# PCM5102A_Breakout.net
KiCad netlist of a schematic drawn in EAGLE
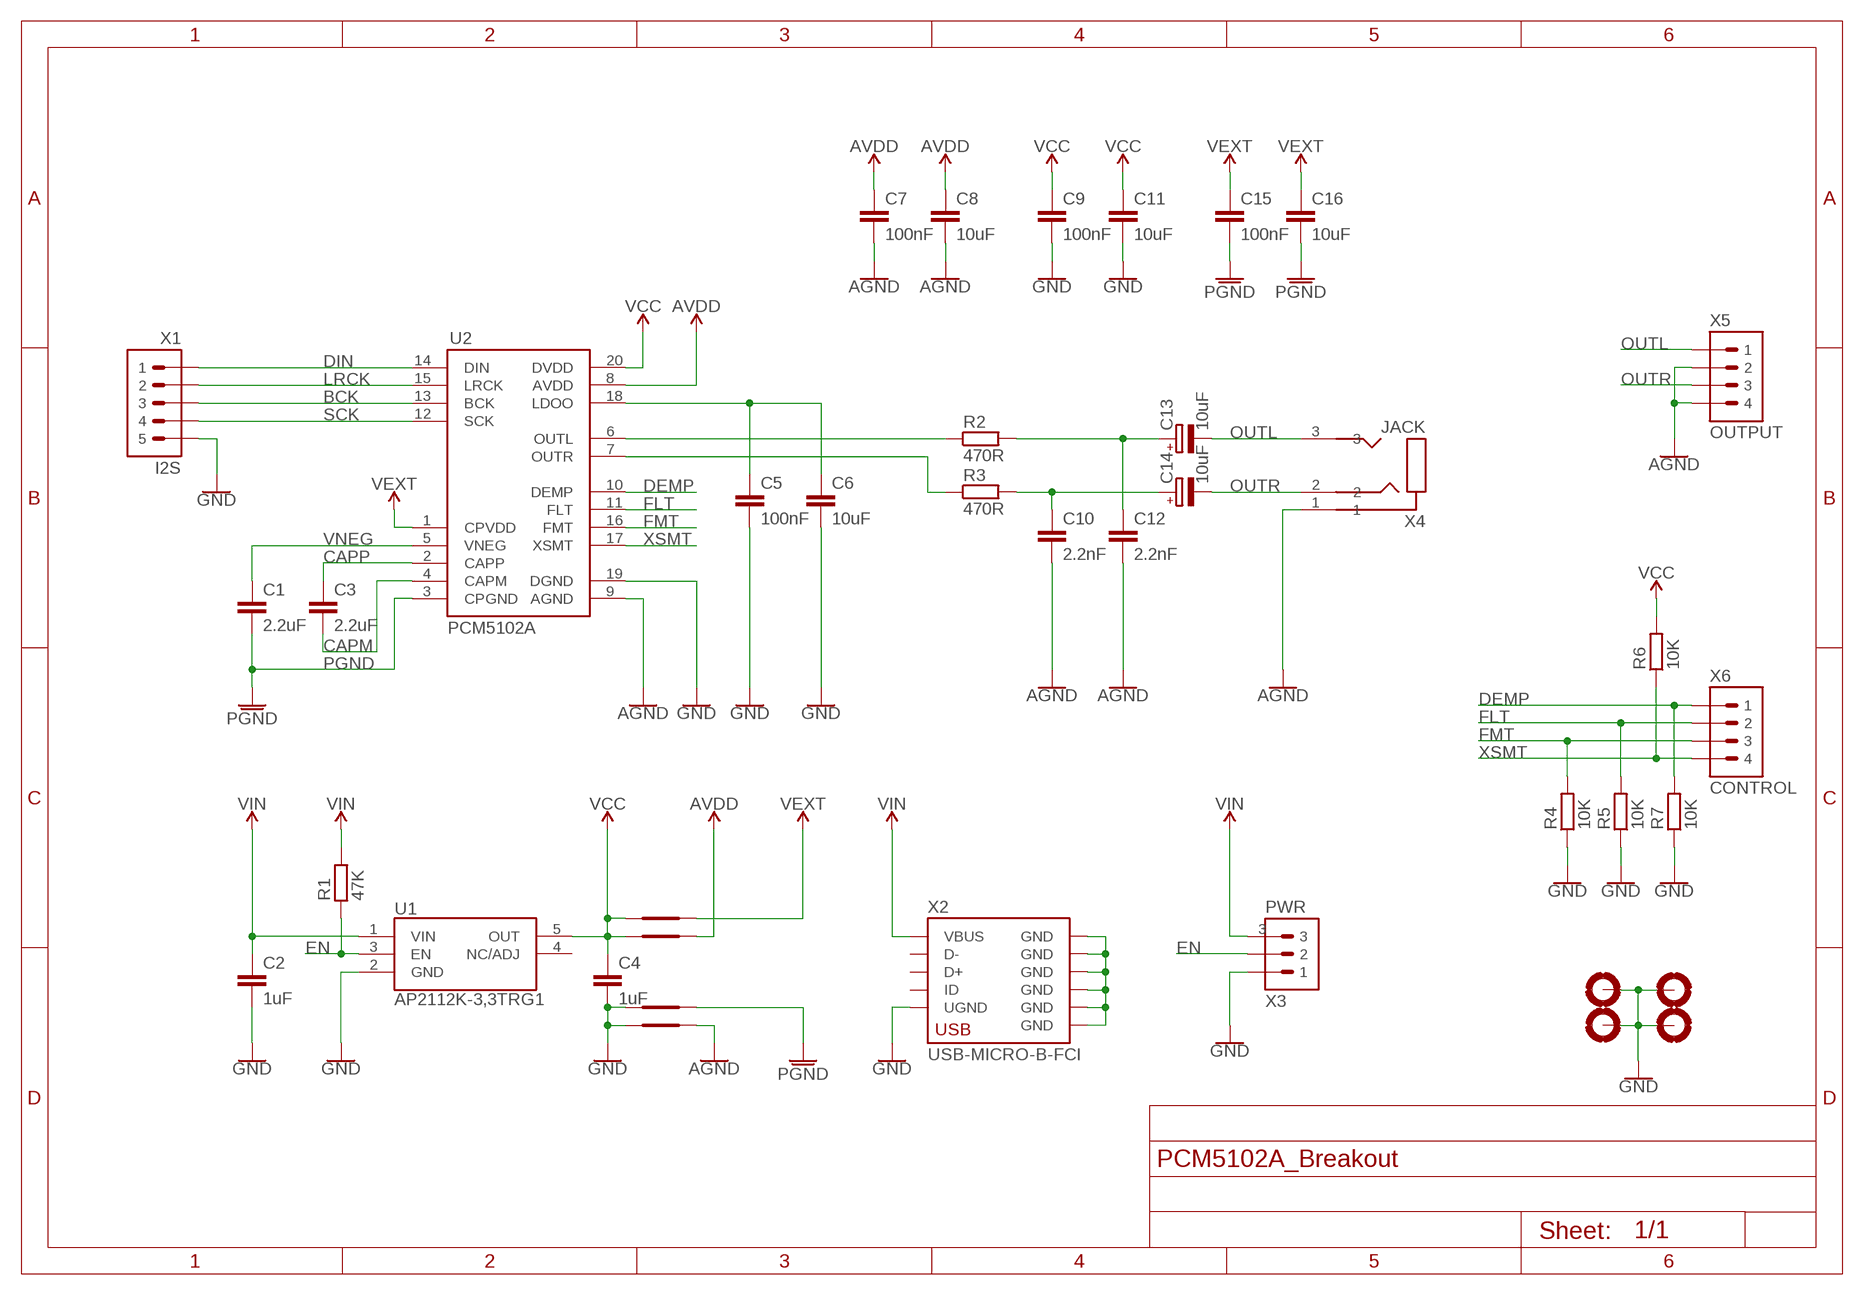
[diagram p0: schematic, sheet 1]

(export (version "E")
  (design (tool "Eeschema 10.0.6"))
  (components
    (comp (ref "C1")
      (value "2.2uF")
      (footprint "eagle-import:C0603")
      (libsource (lib "eagle-import") (part "CAPC0603"))
    )
    (comp (ref "C2")
      (value "1uF")
      (footprint "eagle-import:C0603")
      (libsource (lib "eagle-import") (part "CAPC0603"))
    )
    (comp (ref "C3")
      (value "2.2uF")
      (footprint "eagle-import:C0603")
      (libsource (lib "eagle-import") (part "CAPC0603"))
    )
    (comp (ref "C4")
      (value "1uF")
      (footprint "eagle-import:C0603")
      (libsource (lib "eagle-import") (part "CAPC0603"))
    )
    (comp (ref "C5")
      (value "100nF")
      (footprint "eagle-import:C0603")
      (libsource (lib "eagle-import") (part "CAPC0603"))
    )
    (comp (ref "C6")
      (value "10uF")
      (footprint "eagle-import:C0603")
      (libsource (lib "eagle-import") (part "CAPC0603"))
    )
    (comp (ref "C7")
      (value "100nF")
      (footprint "eagle-import:C0603")
      (libsource (lib "eagle-import") (part "CAPC0603"))
    )
    (comp (ref "C8")
      (value "10uF")
      (footprint "eagle-import:C0603")
      (libsource (lib "eagle-import") (part "CAPC0603"))
    )
    (comp (ref "C9")
      (value "100nF")
      (footprint "eagle-import:C0603")
      (libsource (lib "eagle-import") (part "CAPC0603"))
    )
    (comp (ref "C10")
      (value "2.2nF")
      (footprint "eagle-import:C0603")
      (libsource (lib "eagle-import") (part "CAPC0603"))
    )
    (comp (ref "C11")
      (value "10uF")
      (footprint "eagle-import:C0603")
      (libsource (lib "eagle-import") (part "CAPC0603"))
    )
    (comp (ref "C12")
      (value "2.2nF")
      (footprint "eagle-import:C0603")
      (libsource (lib "eagle-import") (part "CAPC0603"))
    )
    (comp (ref "C13")
      (value "10uF")
      (footprint "eagle-import:ROQANG-RVT0405")
      (libsource (lib "eagle-import") (part "CAP-POL-ALUMROQANG-RVT0405"))
    )
    (comp (ref "C14")
      (value "10uF")
      (footprint "eagle-import:ROQANG-RVT0405")
      (libsource (lib "eagle-import") (part "CAP-POL-ALUMROQANG-RVT0405"))
    )
    (comp (ref "C15")
      (value "100nF")
      (footprint "eagle-import:C0603")
      (libsource (lib "eagle-import") (part "CAPC0603"))
    )
    (comp (ref "C16")
      (value "10uF")
      (footprint "eagle-import:C0603")
      (libsource (lib "eagle-import") (part "CAPC0603"))
    )
    (comp (ref "H1")
      (value "MOUNTHOLE-PAD3.2")
      (footprint "eagle-import:3.2-PAD")
      (libsource (lib "eagle-import") (part "MOUNTHOLE-PAD3.2"))
    )
    (comp (ref "H2")
      (value "MOUNTHOLE-PAD3.2")
      (footprint "eagle-import:3.2-PAD")
      (libsource (lib "eagle-import") (part "MOUNTHOLE-PAD3.2"))
    )
    (comp (ref "H3")
      (value "MOUNTHOLE-PAD3.2")
      (footprint "eagle-import:3.2-PAD")
      (libsource (lib "eagle-import") (part "MOUNTHOLE-PAD3.2"))
    )
    (comp (ref "H4")
      (value "MOUNTHOLE-PAD3.2")
      (footprint "eagle-import:3.2-PAD")
      (libsource (lib "eagle-import") (part "MOUNTHOLE-PAD3.2"))
    )
    (comp (ref "R1")
      (value "47K")
      (footprint "eagle-import:R0603")
      (libsource (lib "eagle-import") (part "RESISTOR0603"))
    )
    (comp (ref "R2")
      (value "470R")
      (footprint "eagle-import:R0603")
      (libsource (lib "eagle-import") (part "RESISTOR0603"))
    )
    (comp (ref "R3")
      (value "470R")
      (footprint "eagle-import:R0603")
      (libsource (lib "eagle-import") (part "RESISTOR0603"))
    )
    (comp (ref "R4")
      (value "10K")
      (footprint "eagle-import:R0603")
      (libsource (lib "eagle-import") (part "RESISTOR0603"))
    )
    (comp (ref "R5")
      (value "10K")
      (footprint "eagle-import:R0603")
      (libsource (lib "eagle-import") (part "RESISTOR0603"))
    )
    (comp (ref "R6")
      (value "10K")
      (footprint "eagle-import:R0603")
      (libsource (lib "eagle-import") (part "RESISTOR0603"))
    )
    (comp (ref "R7")
      (value "10K")
      (footprint "eagle-import:R0603")
      (libsource (lib "eagle-import") (part "RESISTOR0603"))
    )
    (comp (ref "SH1")
      (value "SHORT-SMD-06096")
      (footprint "eagle-import:SHORT-SMD-06096")
      (libsource (lib "eagle-import") (part "SHORT-SMD-06096"))
    )
    (comp (ref "SH2")
      (value "SHORT-SMD-06096")
      (footprint "eagle-import:SHORT-SMD-06096")
      (libsource (lib "eagle-import") (part "SHORT-SMD-06096"))
    )
    (comp (ref "SH3")
      (value "SHORT-SMD-06096")
      (footprint "eagle-import:SHORT-SMD-06096")
      (libsource (lib "eagle-import") (part "SHORT-SMD-06096"))
    )
    (comp (ref "SH4")
      (value "SHORT-SMD-06096")
      (footprint "eagle-import:SHORT-SMD-06096")
      (libsource (lib "eagle-import") (part "SHORT-SMD-06096"))
    )
    (comp (ref "U1")
      (value "AP2112K-3,3TRG1")
      (footprint "eagle-import:SOT23-5")
      (libsource (lib "eagle-import") (part "REGULATOR-AP2112KK-SOT23-5"))
    )
    (comp (ref "U2")
      (value "PCM5102A")
      (footprint "eagle-import:TSSOP-20")
      (libsource (lib "eagle-import") (part "PCM5102APWR"))
    )
    (comp (ref "X1")
      (value "I2S")
      (footprint "eagle-import:1X05-2.54")
      (libsource (lib "eagle-import") (part "HEADER-1X05-2.54"))
    )
    (comp (ref "X2")
      (value "USB-MICRO-B-FCI")
      (footprint "eagle-import:USB-MICRO-B-FCI")
      (libsource (lib "eagle-import") (part "USB-MICRO-B-FCI"))
    )
    (comp (ref "X3")
      (value "PWR")
      (footprint "eagle-import:1X03P-2.54")
      (libsource (lib "eagle-import") (part "HEADER-1X03-2.54P"))
    )
    (comp (ref "X4")
      (value "JACK")
      (footprint "eagle-import:AUDIO-3.5-SJ1-3523N")
      (libsource (lib "eagle-import") (part "AUDIO-3.5-SJ1-3523N"))
    )
    (comp (ref "X5")
      (value "OUTPUT")
      (footprint "eagle-import:1X04-2.54")
      (libsource (lib "eagle-import") (part "HEADER-1X04-2.54"))
    )
    (comp (ref "X6")
      (value "CONTROL")
      (footprint "eagle-import:1X04-2.54")
      (libsource (lib "eagle-import") (part "HEADER-1X04-2.54"))
    )
  )
  (nets
    (net (code "1") (name "/BCK") (class "Default")
      (node (ref "U2") (pin "13") (pinfunction "BCK_13") (pintype "bidirectional"))
      (node (ref "X1") (pin "3") (pinfunction "3_3") (pintype "passive"))
    )
    (net (code "2") (name "/CAPM") (class "Default")
      (node (ref "C3") (pin "2") (pinfunction "2_2") (pintype "passive"))
      (node (ref "U2") (pin "4") (pinfunction "CAPM_4") (pintype "bidirectional"))
    )
    (net (code "3") (name "/CAPP") (class "Default")
      (node (ref "C3") (pin "1") (pinfunction "1_1") (pintype "passive"))
      (node (ref "U2") (pin "2") (pinfunction "CAPP_2") (pintype "bidirectional"))
    )
    (net (code "4") (name "/DEMP") (class "Default")
      (node (ref "R7") (pin "2") (pinfunction "2_2") (pintype "passive"))
      (node (ref "U2") (pin "10") (pinfunction "DEMP_10") (pintype "bidirectional"))
      (node (ref "X6") (pin "1") (pinfunction "1_1") (pintype "passive"))
    )
    (net (code "5") (name "/DIN") (class "Default")
      (node (ref "U2") (pin "14") (pinfunction "DIN_14") (pintype "input"))
      (node (ref "X1") (pin "1") (pinfunction "1_1") (pintype "passive"))
    )
    (net (code "6") (name "/EN") (class "Default")
      (node (ref "R1") (pin "1") (pinfunction "1_1") (pintype "passive"))
      (node (ref "U1") (pin "3") (pinfunction "EN_3") (pintype "input"))
      (node (ref "X3") (pin "2") (pinfunction "2_2") (pintype "passive"))
    )
    (net (code "7") (name "/FLT") (class "Default")
      (node (ref "R5") (pin "2") (pinfunction "2_2") (pintype "passive"))
      (node (ref "U2") (pin "11") (pinfunction "FLT_11") (pintype "bidirectional"))
      (node (ref "X6") (pin "2") (pinfunction "2_2") (pintype "passive"))
    )
    (net (code "8") (name "/FMT") (class "Default")
      (node (ref "R4") (pin "2") (pinfunction "2_2") (pintype "passive"))
      (node (ref "U2") (pin "16") (pinfunction "FMT_16") (pintype "bidirectional"))
      (node (ref "X6") (pin "3") (pinfunction "3_3") (pintype "passive"))
    )
    (net (code "9") (name "/LRCK") (class "Default")
      (node (ref "U2") (pin "15") (pinfunction "LRCK_15") (pintype "bidirectional"))
      (node (ref "X1") (pin "2") (pinfunction "2_2") (pintype "passive"))
    )
    (net (code "10") (name "/OUTL") (class "Default")
      (node (ref "C13") (pin "-") (pinfunction "-_-") (pintype "passive"))
      (node (ref "X4") (pin "3") (pinfunction "3_3") (pintype "bidirectional"))
      (node (ref "X5") (pin "1") (pinfunction "1_1") (pintype "passive"))
    )
    (net (code "11") (name "/OUTR") (class "Default")
      (node (ref "C14") (pin "-") (pinfunction "-_-") (pintype "passive"))
      (node (ref "X4") (pin "2") (pinfunction "2_2") (pintype "bidirectional"))
      (node (ref "X5") (pin "3") (pinfunction "3_3") (pintype "passive"))
    )
    (net (code "12") (name "/SCK") (class "Default")
      (node (ref "U2") (pin "12") (pinfunction "SCK_12") (pintype "input"))
      (node (ref "X1") (pin "4") (pinfunction "4_4") (pintype "passive"))
    )
    (net (code "13") (name "/VNEG") (class "Default")
      (node (ref "C1") (pin "1") (pinfunction "1_1") (pintype "passive"))
      (node (ref "U2") (pin "5") (pinfunction "VNEG_5") (pintype "bidirectional"))
    )
    (net (code "14") (name "/XSMT") (class "Default")
      (node (ref "R6") (pin "1") (pinfunction "1_1") (pintype "passive"))
      (node (ref "U2") (pin "17") (pinfunction "XSMT_17") (pintype "bidirectional"))
      (node (ref "X6") (pin "4") (pinfunction "4_4") (pintype "passive"))
    )
    (net (code "15") (name "AGND") (class "Default")
      (node (ref "C10") (pin "2") (pinfunction "2_2") (pintype "passive"))
      (node (ref "C12") (pin "2") (pinfunction "2_2") (pintype "passive"))
      (node (ref "C7") (pin "2") (pinfunction "2_2") (pintype "passive"))
      (node (ref "C8") (pin "2") (pinfunction "2_2") (pintype "passive"))
      (node (ref "SH4") (pin "2") (pinfunction "P$2_2") (pintype "bidirectional"))
      (node (ref "U2") (pin "9") (pinfunction "AGND_9") (pintype "bidirectional"))
      (node (ref "X4") (pin "1") (pinfunction "1_1") (pintype "bidirectional"))
      (node (ref "X5") (pin "2") (pinfunction "2_2") (pintype "passive"))
      (node (ref "X5") (pin "4") (pinfunction "4_4") (pintype "passive"))
    )
    (net (code "16") (name "AVDD") (class "Default")
      (node (ref "C7") (pin "1") (pinfunction "1_1") (pintype "passive"))
      (node (ref "C8") (pin "1") (pinfunction "1_1") (pintype "passive"))
      (node (ref "SH2") (pin "2") (pinfunction "P$2_2") (pintype "bidirectional"))
      (node (ref "U2") (pin "8") (pinfunction "AVDD_8") (pintype "bidirectional"))
    )
    (net (code "17") (name "GND") (class "Default")
      (node (ref "C11") (pin "2") (pinfunction "2_2") (pintype "passive"))
      (node (ref "C2") (pin "2") (pinfunction "2_2") (pintype "passive"))
      (node (ref "C4") (pin "2") (pinfunction "2_2") (pintype "passive"))
      (node (ref "C5") (pin "2") (pinfunction "2_2") (pintype "passive"))
      (node (ref "C6") (pin "2") (pinfunction "2_2") (pintype "passive"))
      (node (ref "C9") (pin "2") (pinfunction "2_2") (pintype "passive"))
      (node (ref "H1") (pin "B3,2") (pinfunction "MOUNT_B3,2") (pintype "passive"))
      (node (ref "H2") (pin "B3,2") (pinfunction "MOUNT_B3,2") (pintype "passive"))
      (node (ref "H3") (pin "B3,2") (pinfunction "MOUNT_B3,2") (pintype "passive"))
      (node (ref "H4") (pin "B3,2") (pinfunction "MOUNT_B3,2") (pintype "passive"))
      (node (ref "R4") (pin "1") (pinfunction "1_1") (pintype "passive"))
      (node (ref "R5") (pin "1") (pinfunction "1_1") (pintype "passive"))
      (node (ref "R7") (pin "1") (pinfunction "1_1") (pintype "passive"))
      (node (ref "SH3") (pin "1") (pinfunction "P$1_1") (pintype "bidirectional"))
      (node (ref "SH4") (pin "1") (pinfunction "P$1_1") (pintype "bidirectional"))
      (node (ref "U1") (pin "2") (pinfunction "GND_2") (pintype "power_in"))
      (node (ref "U2") (pin "19") (pinfunction "DGND_19") (pintype "bidirectional"))
      (node (ref "X1") (pin "5") (pinfunction "5_5") (pintype "passive"))
      (node (ref "X2") (pin "5") (pinfunction "UGND_5") (pintype "power_in"))
      (node (ref "X3") (pin "1") (pinfunction "1_1") (pintype "passive"))
    )
    (net (code "18") (name "Net-(C10-Pad1)") (class "Default")
      (node (ref "C10") (pin "1") (pinfunction "1_1") (pintype "passive"))
      (node (ref "C14") (pin "+") (pinfunction "+_+") (pintype "passive"))
      (node (ref "R3") (pin "2") (pinfunction "2_2") (pintype "passive"))
    )
    (net (code "19") (name "Net-(C12-Pad1)") (class "Default")
      (node (ref "C12") (pin "1") (pinfunction "1_1") (pintype "passive"))
      (node (ref "C13") (pin "+") (pinfunction "+_+") (pintype "passive"))
      (node (ref "R2") (pin "2") (pinfunction "2_2") (pintype "passive"))
    )
    (net (code "20") (name "Net-(U2-LDOO)") (class "Default")
      (node (ref "C5") (pin "1") (pinfunction "1_1") (pintype "passive"))
      (node (ref "C6") (pin "1") (pinfunction "1_1") (pintype "passive"))
      (node (ref "U2") (pin "18") (pinfunction "LDOO_18") (pintype "bidirectional"))
    )
    (net (code "21") (name "Net-(U2-OUTL)") (class "Default")
      (node (ref "R2") (pin "1") (pinfunction "1_1") (pintype "passive"))
      (node (ref "U2") (pin "6") (pinfunction "OUTL_6") (pintype "bidirectional"))
    )
    (net (code "22") (name "Net-(U2-OUTR)") (class "Default")
      (node (ref "R3") (pin "1") (pinfunction "1_1") (pintype "passive"))
      (node (ref "U2") (pin "7") (pinfunction "OUTR_7") (pintype "bidirectional"))
    )
    (net (code "23") (name "Net-(X2-GND-PadGND@1)") (class "Default")
      (node (ref "X2") (pin "GND@1") (pinfunction "GND_GND@1") (pintype "power_in"))
      (node (ref "X2") (pin "GND@2") (pinfunction "GND_GND@2") (pintype "power_in"))
      (node (ref "X2") (pin "GND@3") (pinfunction "GND_GND@3") (pintype "power_in"))
      (node (ref "X2") (pin "GND@4") (pinfunction "GND_GND@4") (pintype "power_in"))
      (node (ref "X2") (pin "GND@5") (pinfunction "GND_GND@5") (pintype "power_in"))
      (node (ref "X2") (pin "GND@6") (pinfunction "GND_GND@6") (pintype "power_in"))
    )
    (net (code "24") (name "PGND") (class "Default")
      (node (ref "C1") (pin "2") (pinfunction "2_2") (pintype "passive"))
      (node (ref "C15") (pin "2") (pinfunction "2_2") (pintype "passive"))
      (node (ref "C16") (pin "2") (pinfunction "2_2") (pintype "passive"))
      (node (ref "SH3") (pin "2") (pinfunction "P$2_2") (pintype "bidirectional"))
      (node (ref "U2") (pin "3") (pinfunction "CPGND_3") (pintype "bidirectional"))
    )
    (net (code "25") (name "VCC") (class "Default")
      (node (ref "C11") (pin "1") (pinfunction "1_1") (pintype "passive"))
      (node (ref "C4") (pin "1") (pinfunction "1_1") (pintype "passive"))
      (node (ref "C9") (pin "1") (pinfunction "1_1") (pintype "passive"))
      (node (ref "R6") (pin "2") (pinfunction "2_2") (pintype "passive"))
      (node (ref "SH1") (pin "1") (pinfunction "P$1_1") (pintype "bidirectional"))
      (node (ref "SH2") (pin "1") (pinfunction "P$1_1") (pintype "bidirectional"))
      (node (ref "U1") (pin "5") (pinfunction "OUT_5") (pintype "power_in"))
      (node (ref "U2") (pin "20") (pinfunction "DVDD_20") (pintype "bidirectional"))
    )
    (net (code "26") (name "VEXT") (class "Default")
      (node (ref "C15") (pin "1") (pinfunction "1_1") (pintype "passive"))
      (node (ref "C16") (pin "1") (pinfunction "1_1") (pintype "passive"))
      (node (ref "SH1") (pin "2") (pinfunction "P$2_2") (pintype "bidirectional"))
      (node (ref "U2") (pin "1") (pinfunction "CPVDD_1") (pintype "bidirectional"))
    )
    (net (code "27") (name "VIN") (class "Default")
      (node (ref "C2") (pin "1") (pinfunction "1_1") (pintype "passive"))
      (node (ref "R1") (pin "2") (pinfunction "2_2") (pintype "passive"))
      (node (ref "U1") (pin "1") (pinfunction "VIN_1") (pintype "power_in"))
      (node (ref "X2") (pin "1") (pinfunction "VBUS_1") (pintype "power_in"))
      (node (ref "X3") (pin "3") (pinfunction "3_3") (pintype "passive"))
    )
    (net (code "28") (name "unconnected-(U1-NC{slash}ADJ-Pad4)") (class "Default")
      (node (ref "U1") (pin "4") (pinfunction "NC/ADJ_4") (pintype "passive"))
    )
    (net (code "29") (name "unconnected-(X2-D+-Pad3)") (class "Default")
      (node (ref "X2") (pin "3") (pinfunction "D+_3") (pintype "bidirectional"))
    )
    (net (code "30") (name "unconnected-(X2-D--Pad2)") (class "Default")
      (node (ref "X2") (pin "2") (pinfunction "D-_2") (pintype "bidirectional"))
    )
    (net (code "31") (name "unconnected-(X2-ID-Pad4)") (class "Default")
      (node (ref "X2") (pin "4") (pinfunction "ID_4") (pintype "bidirectional"))
    )
  )
)
